# controller.net
KiCad netlist of a schematic drawn in EAGLE
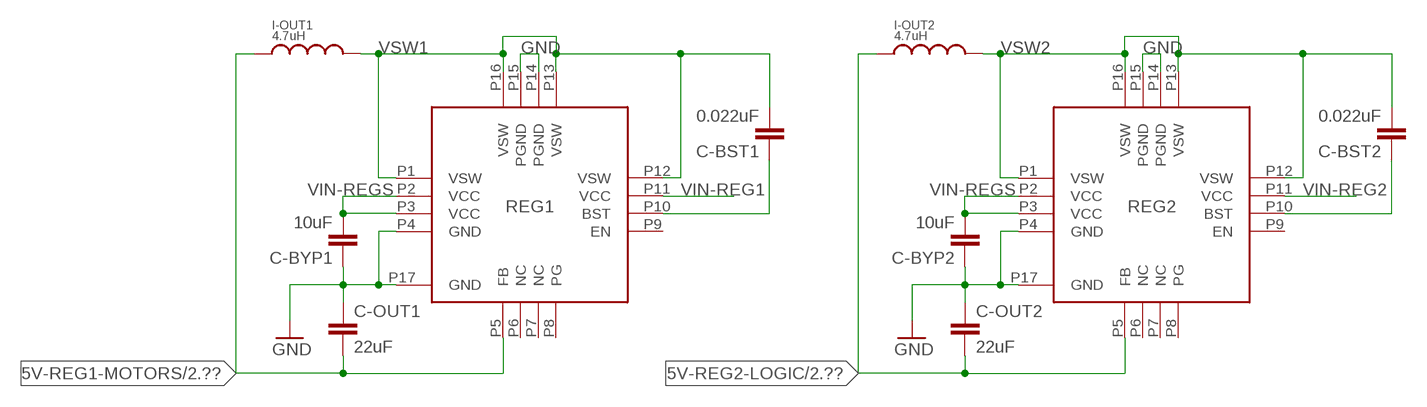
[diagram p0: schematic, sheet 1]
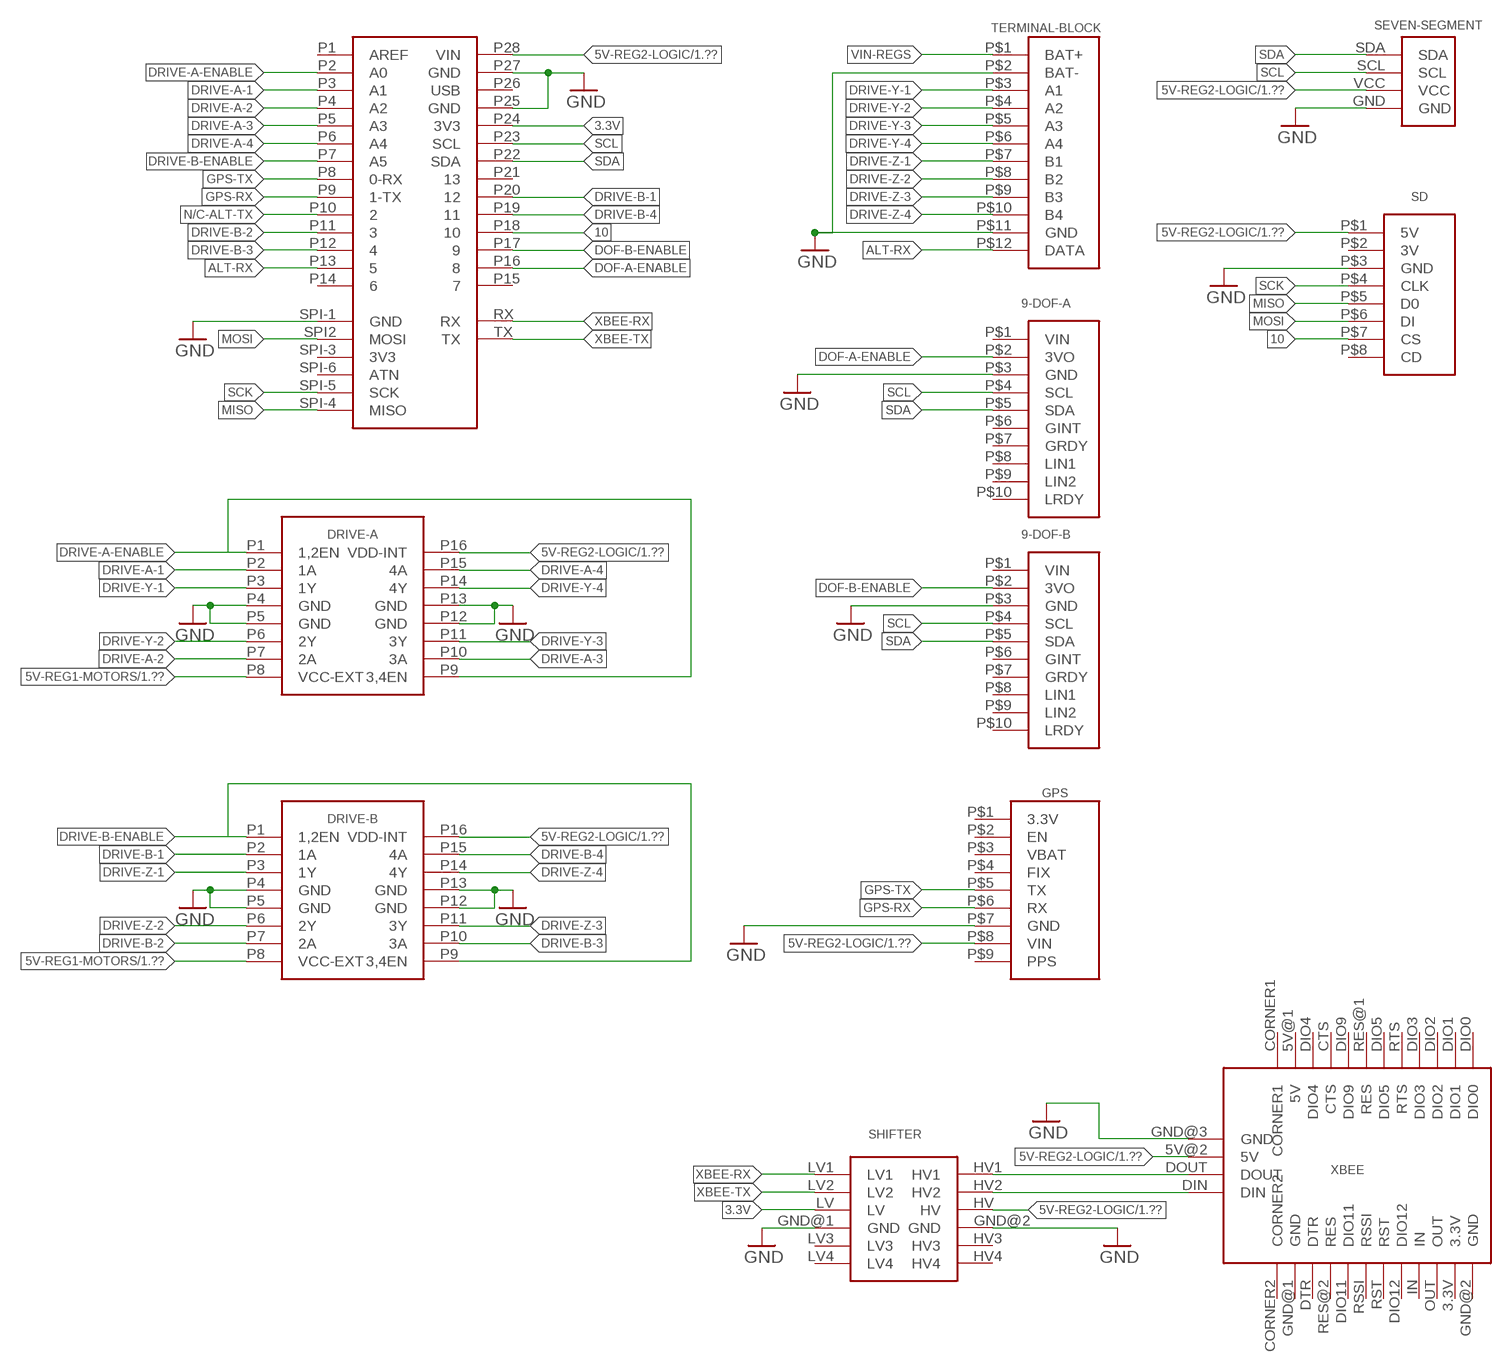
[diagram p1: schematic, sheet 2]

(export (version "E")
  (design (tool "Eeschema 10.0.6"))
  (components
    (comp (ref "9-DOF-A")
      (value "ADAFRUIT-9-DOF")
      (footprint "eagle-import:ADAFRUIT-9-DOF")
      (fields (field (name "MANF") "Adafruit"))
      (libsource (lib "eagle-import") (part "ADAFRUIT-9-DOF"))
    )
    (comp (ref "9-DOF-B")
      (value "ADAFRUIT-9-DOF")
      (footprint "eagle-import:ADAFRUIT-9-DOF")
      (fields (field (name "MANF") "Adafruit"))
      (libsource (lib "eagle-import") (part "ADAFRUIT-9-DOF"))
    )
    (comp (ref "DRIVE-A")
      (value "SN754410")
      (footprint "eagle-import:SN754410")
      (fields (field (name "MANF") "Texas Instruments"))
      (libsource (lib "eagle-import") (part "SN754410"))
    )
    (comp (ref "DRIVE-B")
      (value "SN754410")
      (footprint "eagle-import:SN754410")
      (fields (field (name "MANF") "Texas Instruments"))
      (libsource (lib "eagle-import") (part "SN754410"))
    )
    (comp (ref "GPS")
      (value "ADAFRUIT-GPS-BREAKOUT")
      (footprint "eagle-import:ADAFRUIT-GPS-BREAKOUT")
      (libsource (lib "eagle-import") (part "ADAFRUIT-GPS-BREAKOUT"))
    )
    (comp (ref "NEUTRINO")
      (value "NEUTRINO")
      (footprint "eagle-import:NEUTRINO")
      (libsource (lib "eagle-import") (part "NEUTRINO"))
    )
    (comp (ref "SD")
      (value "ADAFRUIT-MICRO-SD")
      (footprint "eagle-import:ADAFRUIT-MICRO-SD")
      (libsource (lib "eagle-import") (part "ADAFRUIT-MICRO-SD"))
    )
    (comp (ref "SEVEN-SEGMENT")
      (value "ADAFRUIT-7-SEGMENT")
      (footprint "eagle-import:ADAFRUIT-7-SEGMENT")
      (libsource (lib "eagle-import") (part "ADAFRUIT-7-SEGMENT"))
    )
    (comp (ref "SHIFTER")
      (value "SPARKFUN-LEVEL-SHIFTER")
      (footprint "eagle-import:SPARKFUN-LEVEL-SHIFTER")
      (libsource (lib "eagle-import") (part "SPARKFUN-LEVEL-SHIFTER"))
    )
    (comp (ref "TERMINAL-BLOCK")
      (value "1725753")
      (footprint "eagle-import:1725753")
      (fields (field (name "MANF") "Phoenix Contact"))
      (libsource (lib "eagle-import") (part "1725753"))
    )
    (comp (ref "XBEE")
      (value "XBEE-BREAKOUT")
      (footprint "eagle-import:XBEE-BREAKOUT")
      (libsource (lib "eagle-import") (part "XBEE-BREAKOUT"))
    )
    (comp (ref "C-BST1")
      (value "0.022uF")
      (footprint "eagle-import:C1608")
      (fields (field (name "MANF") "Samsung Electro-Mechanics America, Inc."))
      (libsource (lib "eagle-import") (part "C-EUC1608"))
    )
    (comp (ref "C-BST2")
      (value "0.022uF")
      (footprint "eagle-import:C1608")
      (fields (field (name "MANF") "Samsung Electro-Mechanics America, Inc."))
      (libsource (lib "eagle-import") (part "C-EUC1608"))
    )
    (comp (ref "C-BYP1")
      (value "10uF")
      (footprint "eagle-import:C3216")
      (fields (field (name "MANF") "Murata Electronics North America"))
      (libsource (lib "eagle-import") (part "C-EUC3216"))
    )
    (comp (ref "C-BYP2")
      (value "10uF")
      (footprint "eagle-import:C3216")
      (fields (field (name "MANF") "Murata Electronics North America"))
      (libsource (lib "eagle-import") (part "C-EUC3216"))
    )
    (comp (ref "C-OUT1")
      (value "22uF")
      (footprint "eagle-import:C2012")
      (fields (field (name "MANF") "TDK Corporation"))
      (libsource (lib "eagle-import") (part "C-EUC2012"))
    )
    (comp (ref "C-OUT2")
      (value "22uF")
      (footprint "eagle-import:C2012")
      (fields (field (name "MANF") "TDK Corporation"))
      (libsource (lib "eagle-import") (part "C-EUC2012"))
    )
    (comp (ref "I-OUT1")
      (value "4.7uH")
      (footprint "eagle-import:ASPI-0628-4R7M-T1")
      (fields (field (name "MANF") "Abracon LLC"))
      (libsource (lib "eagle-import") (part "ASPI-0628-4R7M-T1"))
    )
    (comp (ref "I-OUT2")
      (value "4.7uH")
      (footprint "eagle-import:ASPI-0628-4R7M-T1")
      (fields (field (name "MANF") "Abracon LLC"))
      (libsource (lib "eagle-import") (part "ASPI-0628-4R7M-T1"))
    )
    (comp (ref "REG1")
      (value "TS30012-M050QFNR")
      (footprint "eagle-import:TS30012-M050QFNR")
      (fields (field (name "MANF") "Semtech Corporation"))
      (libsource (lib "eagle-import") (part "TS30012-M050QFNR"))
    )
    (comp (ref "REG2")
      (value "TS30012-M050QFNR")
      (footprint "eagle-import:TS30012-M050QFNR")
      (fields (field (name "MANF") "Semtech Corporation"))
      (libsource (lib "eagle-import") (part "TS30012-M050QFNR"))
    )
  )
  (nets
    (net (code "1") (name "3.3V") (class "Default")
      (node (ref "NEUTRINO") (pin "P24") (pinfunction "3V3_P24") (pintype "bidirectional"))
      (node (ref "SHIFTER") (pin "LV") (pinfunction "LV_LV") (pintype "bidirectional"))
    )
    (net (code "2") (name "5V-REG1-MOTORS") (class "Default")
      (node (ref "C-OUT1") (pin "2") (pinfunction "2_2") (pintype "passive"))
      (node (ref "DRIVE-A") (pin "P8") (pinfunction "VCC-EXT_P8") (pintype "bidirectional"))
      (node (ref "DRIVE-B") (pin "P8") (pinfunction "VCC-EXT_P8") (pintype "bidirectional"))
      (node (ref "I-OUT1") (pin "P$1") (pinfunction "P$1_P$1") (pintype "bidirectional"))
      (node (ref "REG1") (pin "P5") (pinfunction "FB_P5") (pintype "bidirectional"))
    )
    (net (code "3") (name "5V-REG2-LOGIC") (class "Default")
      (node (ref "C-OUT2") (pin "2") (pinfunction "2_2") (pintype "passive"))
      (node (ref "DRIVE-A") (pin "P16") (pinfunction "VDD-INT_P16") (pintype "bidirectional"))
      (node (ref "DRIVE-B") (pin "P16") (pinfunction "VDD-INT_P16") (pintype "bidirectional"))
      (node (ref "GPS") (pin "P$8") (pinfunction "VIN_P$8") (pintype "bidirectional"))
      (node (ref "I-OUT2") (pin "P$1") (pinfunction "P$1_P$1") (pintype "bidirectional"))
      (node (ref "NEUTRINO") (pin "P28") (pinfunction "VIN_P28") (pintype "bidirectional"))
      (node (ref "REG2") (pin "P5") (pinfunction "FB_P5") (pintype "bidirectional"))
      (node (ref "SD") (pin "P$1") (pinfunction "5V_P$1") (pintype "bidirectional"))
      (node (ref "SEVEN-SEGMENT") (pin "VCC") (pinfunction "VCC_VCC") (pintype "bidirectional"))
      (node (ref "SHIFTER") (pin "HV") (pinfunction "HV_HV") (pintype "bidirectional"))
      (node (ref "XBEE") (pin "5V@2") (pinfunction "5V_5V@2") (pintype "bidirectional"))
    )
    (net (code "4") (name "10") (class "Default")
      (node (ref "NEUTRINO") (pin "P18") (pinfunction "10_P18") (pintype "bidirectional"))
      (node (ref "SD") (pin "P$7") (pinfunction "CS_P$7") (pintype "bidirectional"))
    )
    (net (code "5") (name "ALT-RX") (class "Default")
      (node (ref "NEUTRINO") (pin "P13") (pinfunction "5_P13") (pintype "bidirectional"))
      (node (ref "TERMINAL-BLOCK") (pin "P$12") (pinfunction "DATA_P$12") (pintype "bidirectional"))
    )
    (net (code "6") (name "DOF-A-ENABLE") (class "Default")
      (node (ref "9-DOF-A") (pin "P$2") (pinfunction "3VO_P$2") (pintype "bidirectional"))
      (node (ref "NEUTRINO") (pin "P16") (pinfunction "8_P16") (pintype "bidirectional"))
    )
    (net (code "7") (name "DOF-B-ENABLE") (class "Default")
      (node (ref "9-DOF-B") (pin "P$2") (pinfunction "3VO_P$2") (pintype "bidirectional"))
      (node (ref "NEUTRINO") (pin "P17") (pinfunction "9_P17") (pintype "bidirectional"))
    )
    (net (code "8") (name "DRIVE-A-1") (class "Default")
      (node (ref "DRIVE-A") (pin "P2") (pinfunction "1A_P2") (pintype "bidirectional"))
      (node (ref "NEUTRINO") (pin "P3") (pinfunction "A1_P3") (pintype "bidirectional"))
    )
    (net (code "9") (name "DRIVE-A-2") (class "Default")
      (node (ref "DRIVE-A") (pin "P7") (pinfunction "2A_P7") (pintype "bidirectional"))
      (node (ref "NEUTRINO") (pin "P4") (pinfunction "A2_P4") (pintype "bidirectional"))
    )
    (net (code "10") (name "DRIVE-A-3") (class "Default")
      (node (ref "DRIVE-A") (pin "P10") (pinfunction "3A_P10") (pintype "bidirectional"))
      (node (ref "NEUTRINO") (pin "P5") (pinfunction "A3_P5") (pintype "bidirectional"))
    )
    (net (code "11") (name "DRIVE-A-4") (class "Default")
      (node (ref "DRIVE-A") (pin "P15") (pinfunction "4A_P15") (pintype "bidirectional"))
      (node (ref "NEUTRINO") (pin "P6") (pinfunction "A4_P6") (pintype "bidirectional"))
    )
    (net (code "12") (name "DRIVE-A-ENABLE") (class "Default")
      (node (ref "DRIVE-A") (pin "P1") (pinfunction "1,2EN_P1") (pintype "bidirectional"))
      (node (ref "DRIVE-A") (pin "P9") (pinfunction "3,4EN_P9") (pintype "bidirectional"))
      (node (ref "NEUTRINO") (pin "P2") (pinfunction "A0_P2") (pintype "bidirectional"))
    )
    (net (code "13") (name "DRIVE-B-1") (class "Default")
      (node (ref "DRIVE-B") (pin "P2") (pinfunction "1A_P2") (pintype "bidirectional"))
      (node (ref "NEUTRINO") (pin "P20") (pinfunction "12_P20") (pintype "bidirectional"))
    )
    (net (code "14") (name "DRIVE-B-2") (class "Default")
      (node (ref "DRIVE-B") (pin "P7") (pinfunction "2A_P7") (pintype "bidirectional"))
      (node (ref "NEUTRINO") (pin "P11") (pinfunction "3_P11") (pintype "bidirectional"))
    )
    (net (code "15") (name "DRIVE-B-3") (class "Default")
      (node (ref "DRIVE-B") (pin "P10") (pinfunction "3A_P10") (pintype "bidirectional"))
      (node (ref "NEUTRINO") (pin "P12") (pinfunction "4_P12") (pintype "bidirectional"))
    )
    (net (code "16") (name "DRIVE-B-4") (class "Default")
      (node (ref "DRIVE-B") (pin "P15") (pinfunction "4A_P15") (pintype "bidirectional"))
      (node (ref "NEUTRINO") (pin "P19") (pinfunction "11_P19") (pintype "bidirectional"))
    )
    (net (code "17") (name "DRIVE-B-ENABLE") (class "Default")
      (node (ref "DRIVE-B") (pin "P1") (pinfunction "1,2EN_P1") (pintype "bidirectional"))
      (node (ref "DRIVE-B") (pin "P9") (pinfunction "3,4EN_P9") (pintype "bidirectional"))
      (node (ref "NEUTRINO") (pin "P7") (pinfunction "A5_P7") (pintype "bidirectional"))
    )
    (net (code "18") (name "DRIVE-Y-1") (class "Default")
      (node (ref "DRIVE-A") (pin "P3") (pinfunction "1Y_P3") (pintype "bidirectional"))
      (node (ref "TERMINAL-BLOCK") (pin "P$3") (pinfunction "A1_P$3") (pintype "bidirectional"))
    )
    (net (code "19") (name "DRIVE-Y-2") (class "Default")
      (node (ref "DRIVE-A") (pin "P6") (pinfunction "2Y_P6") (pintype "bidirectional"))
      (node (ref "TERMINAL-BLOCK") (pin "P$4") (pinfunction "A2_P$4") (pintype "bidirectional"))
    )
    (net (code "20") (name "DRIVE-Y-3") (class "Default")
      (node (ref "DRIVE-A") (pin "P11") (pinfunction "3Y_P11") (pintype "bidirectional"))
      (node (ref "TERMINAL-BLOCK") (pin "P$5") (pinfunction "A3_P$5") (pintype "bidirectional"))
    )
    (net (code "21") (name "DRIVE-Y-4") (class "Default")
      (node (ref "DRIVE-A") (pin "P14") (pinfunction "4Y_P14") (pintype "bidirectional"))
      (node (ref "TERMINAL-BLOCK") (pin "P$6") (pinfunction "A4_P$6") (pintype "bidirectional"))
    )
    (net (code "22") (name "DRIVE-Z-1") (class "Default")
      (node (ref "DRIVE-B") (pin "P3") (pinfunction "1Y_P3") (pintype "bidirectional"))
      (node (ref "TERMINAL-BLOCK") (pin "P$7") (pinfunction "B1_P$7") (pintype "bidirectional"))
    )
    (net (code "23") (name "DRIVE-Z-2") (class "Default")
      (node (ref "DRIVE-B") (pin "P6") (pinfunction "2Y_P6") (pintype "bidirectional"))
      (node (ref "TERMINAL-BLOCK") (pin "P$8") (pinfunction "B2_P$8") (pintype "bidirectional"))
    )
    (net (code "24") (name "DRIVE-Z-3") (class "Default")
      (node (ref "DRIVE-B") (pin "P11") (pinfunction "3Y_P11") (pintype "bidirectional"))
      (node (ref "TERMINAL-BLOCK") (pin "P$9") (pinfunction "B3_P$9") (pintype "bidirectional"))
    )
    (net (code "25") (name "DRIVE-Z-4") (class "Default")
      (node (ref "DRIVE-B") (pin "P14") (pinfunction "4Y_P14") (pintype "bidirectional"))
      (node (ref "TERMINAL-BLOCK") (pin "P$10") (pinfunction "B4_P$10") (pintype "bidirectional"))
    )
    (net (code "26") (name "GND") (class "Default")
      (node (ref "9-DOF-A") (pin "P$3") (pinfunction "GND_P$3") (pintype "bidirectional"))
      (node (ref "9-DOF-B") (pin "P$3") (pinfunction "GND_P$3") (pintype "bidirectional"))
      (node (ref "C-BYP1") (pin "1") (pinfunction "1_1") (pintype "passive"))
      (node (ref "C-BYP2") (pin "1") (pinfunction "1_1") (pintype "passive"))
      (node (ref "C-OUT1") (pin "1") (pinfunction "1_1") (pintype "passive"))
      (node (ref "C-OUT2") (pin "1") (pinfunction "1_1") (pintype "passive"))
      (node (ref "DRIVE-A") (pin "P12") (pinfunction "GND_P12") (pintype "bidirectional"))
      (node (ref "DRIVE-A") (pin "P13") (pinfunction "GND_P13") (pintype "bidirectional"))
      (node (ref "DRIVE-A") (pin "P4") (pinfunction "GND_P4") (pintype "bidirectional"))
      (node (ref "DRIVE-A") (pin "P5") (pinfunction "GND_P5") (pintype "bidirectional"))
      (node (ref "DRIVE-B") (pin "P12") (pinfunction "GND_P12") (pintype "bidirectional"))
      (node (ref "DRIVE-B") (pin "P13") (pinfunction "GND_P13") (pintype "bidirectional"))
      (node (ref "DRIVE-B") (pin "P4") (pinfunction "GND_P4") (pintype "bidirectional"))
      (node (ref "DRIVE-B") (pin "P5") (pinfunction "GND_P5") (pintype "bidirectional"))
      (node (ref "GPS") (pin "P$7") (pinfunction "GND_P$7") (pintype "bidirectional"))
      (node (ref "NEUTRINO") (pin "P25") (pinfunction "GND_P25") (pintype "bidirectional"))
      (node (ref "NEUTRINO") (pin "P27") (pinfunction "GND_P27") (pintype "bidirectional"))
      (node (ref "NEUTRINO") (pin "SPI-1") (pinfunction "GND_SPI-1") (pintype "bidirectional"))
      (node (ref "REG1") (pin "P14") (pinfunction "PGND_P14") (pintype "bidirectional"))
      (node (ref "REG1") (pin "P15") (pinfunction "PGND_P15") (pintype "bidirectional"))
      (node (ref "REG1") (pin "P17") (pinfunction "GND_P17") (pintype "bidirectional"))
      (node (ref "REG1") (pin "P4") (pinfunction "GND_P4") (pintype "bidirectional"))
      (node (ref "REG2") (pin "P14") (pinfunction "PGND_P14") (pintype "bidirectional"))
      (node (ref "REG2") (pin "P15") (pinfunction "PGND_P15") (pintype "bidirectional"))
      (node (ref "REG2") (pin "P17") (pinfunction "GND_P17") (pintype "bidirectional"))
      (node (ref "REG2") (pin "P4") (pinfunction "GND_P4") (pintype "bidirectional"))
      (node (ref "SD") (pin "P$3") (pinfunction "GND_P$3") (pintype "bidirectional"))
      (node (ref "SEVEN-SEGMENT") (pin "GND") (pinfunction "GND_GND") (pintype "bidirectional"))
      (node (ref "SHIFTER") (pin "GND@1") (pinfunction "GND_GND@1") (pintype "bidirectional"))
      (node (ref "SHIFTER") (pin "GND@2") (pinfunction "GND_GND@2") (pintype "bidirectional"))
      (node (ref "TERMINAL-BLOCK") (pin "P$11") (pinfunction "GND_P$11") (pintype "bidirectional"))
      (node (ref "TERMINAL-BLOCK") (pin "P$2") (pinfunction "BAT-_P$2") (pintype "bidirectional"))
      (node (ref "XBEE") (pin "GND@3") (pinfunction "GND_GND@3") (pintype "bidirectional"))
    )
    (net (code "27") (name "GPS-RX") (class "Default")
      (node (ref "GPS") (pin "P$6") (pinfunction "RX_P$6") (pintype "bidirectional"))
      (node (ref "NEUTRINO") (pin "P9") (pinfunction "1-TX_P9") (pintype "bidirectional"))
    )
    (net (code "28") (name "GPS-TX") (class "Default")
      (node (ref "GPS") (pin "P$5") (pinfunction "TX_P$5") (pintype "bidirectional"))
      (node (ref "NEUTRINO") (pin "P8") (pinfunction "0-RX_P8") (pintype "bidirectional"))
    )
    (net (code "29") (name "MISO") (class "Default")
      (node (ref "NEUTRINO") (pin "SPI-4") (pinfunction "MISO_SPI-4") (pintype "bidirectional"))
      (node (ref "SD") (pin "P$5") (pinfunction "D0_P$5") (pintype "bidirectional"))
    )
    (net (code "30") (name "MOSI") (class "Default")
      (node (ref "NEUTRINO") (pin "SPI2") (pinfunction "MOSI_SPI2") (pintype "bidirectional"))
      (node (ref "SD") (pin "P$6") (pinfunction "DI_P$6") (pintype "bidirectional"))
    )
    (net (code "31") (name "Net-(REG1-BST)") (class "Default")
      (node (ref "C-BST1") (pin "1") (pinfunction "1_1") (pintype "passive"))
      (node (ref "REG1") (pin "P10") (pinfunction "BST_P10") (pintype "bidirectional"))
    )
    (net (code "32") (name "Net-(REG2-BST)") (class "Default")
      (node (ref "C-BST2") (pin "1") (pinfunction "1_1") (pintype "passive"))
      (node (ref "REG2") (pin "P10") (pinfunction "BST_P10") (pintype "bidirectional"))
    )
    (net (code "33") (name "Net-(SHIFTER-PadHV1)") (class "Default")
      (node (ref "SHIFTER") (pin "HV1") (pinfunction "HV1_HV1") (pintype "bidirectional"))
      (node (ref "XBEE") (pin "DOUT") (pinfunction "DOUT_DOUT") (pintype "bidirectional"))
    )
    (net (code "34") (name "Net-(SHIFTER-PadHV2)") (class "Default")
      (node (ref "SHIFTER") (pin "HV2") (pinfunction "HV2_HV2") (pintype "bidirectional"))
      (node (ref "XBEE") (pin "DIN") (pinfunction "DIN_DIN") (pintype "bidirectional"))
    )
    (net (code "35") (name "N{slash}C-ALT-TX") (class "Default")
      (node (ref "NEUTRINO") (pin "P10") (pinfunction "2_P10") (pintype "bidirectional"))
    )
    (net (code "36") (name "SCK") (class "Default")
      (node (ref "NEUTRINO") (pin "SPI-5") (pinfunction "SCK_SPI-5") (pintype "bidirectional"))
      (node (ref "SD") (pin "P$4") (pinfunction "CLK_P$4") (pintype "bidirectional"))
    )
    (net (code "37") (name "SCL") (class "Default")
      (node (ref "9-DOF-A") (pin "P$4") (pinfunction "SCL_P$4") (pintype "bidirectional"))
      (node (ref "9-DOF-B") (pin "P$4") (pinfunction "SCL_P$4") (pintype "bidirectional"))
      (node (ref "NEUTRINO") (pin "P23") (pinfunction "SCL_P23") (pintype "bidirectional"))
      (node (ref "SEVEN-SEGMENT") (pin "SCL") (pinfunction "SCL_SCL") (pintype "bidirectional"))
    )
    (net (code "38") (name "SDA") (class "Default")
      (node (ref "9-DOF-A") (pin "P$5") (pinfunction "SDA_P$5") (pintype "bidirectional"))
      (node (ref "9-DOF-B") (pin "P$5") (pinfunction "SDA_P$5") (pintype "bidirectional"))
      (node (ref "NEUTRINO") (pin "P22") (pinfunction "SDA_P22") (pintype "bidirectional"))
      (node (ref "SEVEN-SEGMENT") (pin "SDA") (pinfunction "SDA_SDA") (pintype "bidirectional"))
    )
    (net (code "39") (name "VIN-REG1") (class "Default")
      (node (ref "REG1") (pin "P11") (pinfunction "VCC_P11") (pintype "bidirectional"))
    )
    (net (code "40") (name "VIN-REG2") (class "Default")
      (node (ref "REG2") (pin "P11") (pinfunction "VCC_P11") (pintype "bidirectional"))
    )
    (net (code "41") (name "VIN-REGS") (class "Default")
      (node (ref "C-BYP1") (pin "2") (pinfunction "2_2") (pintype "passive"))
      (node (ref "C-BYP2") (pin "2") (pinfunction "2_2") (pintype "passive"))
      (node (ref "REG1") (pin "P2") (pinfunction "VCC_P2") (pintype "bidirectional"))
      (node (ref "REG1") (pin "P3") (pinfunction "VCC_P3") (pintype "bidirectional"))
      (node (ref "REG2") (pin "P2") (pinfunction "VCC_P2") (pintype "bidirectional"))
      (node (ref "REG2") (pin "P3") (pinfunction "VCC_P3") (pintype "bidirectional"))
      (node (ref "TERMINAL-BLOCK") (pin "P$1") (pinfunction "BAT+_P$1") (pintype "bidirectional"))
    )
    (net (code "42") (name "VSW1") (class "Default")
      (node (ref "C-BST1") (pin "2") (pinfunction "2_2") (pintype "passive"))
      (node (ref "I-OUT1") (pin "P$2") (pinfunction "P$2_P$2") (pintype "bidirectional"))
      (node (ref "REG1") (pin "P1") (pinfunction "VSW_P1") (pintype "bidirectional"))
      (node (ref "REG1") (pin "P12") (pinfunction "VSW_P12") (pintype "bidirectional"))
      (node (ref "REG1") (pin "P13") (pinfunction "VSW_P13") (pintype "bidirectional"))
      (node (ref "REG1") (pin "P16") (pinfunction "VSW_P16") (pintype "bidirectional"))
    )
    (net (code "43") (name "VSW2") (class "Default")
      (node (ref "C-BST2") (pin "2") (pinfunction "2_2") (pintype "passive"))
      (node (ref "I-OUT2") (pin "P$2") (pinfunction "P$2_P$2") (pintype "bidirectional"))
      (node (ref "REG2") (pin "P1") (pinfunction "VSW_P1") (pintype "bidirectional"))
      (node (ref "REG2") (pin "P12") (pinfunction "VSW_P12") (pintype "bidirectional"))
      (node (ref "REG2") (pin "P13") (pinfunction "VSW_P13") (pintype "bidirectional"))
      (node (ref "REG2") (pin "P16") (pinfunction "VSW_P16") (pintype "bidirectional"))
    )
    (net (code "44") (name "XBEE-RX") (class "Default")
      (node (ref "NEUTRINO") (pin "RX") (pinfunction "RX_RX") (pintype "bidirectional"))
      (node (ref "SHIFTER") (pin "LV1") (pinfunction "LV1_LV1") (pintype "bidirectional"))
    )
    (net (code "45") (name "XBEE-TX") (class "Default")
      (node (ref "NEUTRINO") (pin "TX") (pinfunction "TX_TX") (pintype "bidirectional"))
      (node (ref "SHIFTER") (pin "LV2") (pinfunction "LV2_LV2") (pintype "bidirectional"))
    )
    (net (code "46") (name "unconnected-(9-DOF-A-GINT-PadP$6)") (class "Default")
      (node (ref "9-DOF-A") (pin "P$6") (pinfunction "GINT_P$6") (pintype "bidirectional"))
    )
    (net (code "47") (name "unconnected-(9-DOF-A-GRDY-PadP$7)") (class "Default")
      (node (ref "9-DOF-A") (pin "P$7") (pinfunction "GRDY_P$7") (pintype "bidirectional"))
    )
    (net (code "48") (name "unconnected-(9-DOF-A-LIN1-PadP$8)") (class "Default")
      (node (ref "9-DOF-A") (pin "P$8") (pinfunction "LIN1_P$8") (pintype "bidirectional"))
    )
    (net (code "49") (name "unconnected-(9-DOF-A-LIN2-PadP$9)") (class "Default")
      (node (ref "9-DOF-A") (pin "P$9") (pinfunction "LIN2_P$9") (pintype "bidirectional"))
    )
    (net (code "50") (name "unconnected-(9-DOF-A-LRDY-PadP$10)") (class "Default")
      (node (ref "9-DOF-A") (pin "P$10") (pinfunction "LRDY_P$10") (pintype "bidirectional"))
    )
    (net (code "51") (name "unconnected-(9-DOF-A-VIN-PadP$1)") (class "Default")
      (node (ref "9-DOF-A") (pin "P$1") (pinfunction "VIN_P$1") (pintype "bidirectional"))
    )
    (net (code "52") (name "unconnected-(9-DOF-B-GINT-PadP$6)") (class "Default")
      (node (ref "9-DOF-B") (pin "P$6") (pinfunction "GINT_P$6") (pintype "bidirectional"))
    )
    (net (code "53") (name "unconnected-(9-DOF-B-GRDY-PadP$7)") (class "Default")
      (node (ref "9-DOF-B") (pin "P$7") (pinfunction "GRDY_P$7") (pintype "bidirectional"))
    )
    (net (code "54") (name "unconnected-(9-DOF-B-LIN1-PadP$8)") (class "Default")
      (node (ref "9-DOF-B") (pin "P$8") (pinfunction "LIN1_P$8") (pintype "bidirectional"))
    )
    (net (code "55") (name "unconnected-(9-DOF-B-LIN2-PadP$9)") (class "Default")
      (node (ref "9-DOF-B") (pin "P$9") (pinfunction "LIN2_P$9") (pintype "bidirectional"))
    )
    (net (code "56") (name "unconnected-(9-DOF-B-LRDY-PadP$10)") (class "Default")
      (node (ref "9-DOF-B") (pin "P$10") (pinfunction "LRDY_P$10") (pintype "bidirectional"))
    )
    (net (code "57") (name "unconnected-(9-DOF-B-VIN-PadP$1)") (class "Default")
      (node (ref "9-DOF-B") (pin "P$1") (pinfunction "VIN_P$1") (pintype "bidirectional"))
    )
    (net (code "58") (name "unconnected-(GPS-3.3V-PadP$1)") (class "Default")
      (node (ref "GPS") (pin "P$1") (pinfunction "3.3V_P$1") (pintype "bidirectional"))
    )
    (net (code "59") (name "unconnected-(GPS-EN-PadP$2)") (class "Default")
      (node (ref "GPS") (pin "P$2") (pinfunction "EN_P$2") (pintype "bidirectional"))
    )
    (net (code "60") (name "unconnected-(GPS-FIX-PadP$4)") (class "Default")
      (node (ref "GPS") (pin "P$4") (pinfunction "FIX_P$4") (pintype "bidirectional"))
    )
    (net (code "61") (name "unconnected-(GPS-PPS-PadP$9)") (class "Default")
      (node (ref "GPS") (pin "P$9") (pinfunction "PPS_P$9") (pintype "bidirectional"))
    )
    (net (code "62") (name "unconnected-(GPS-VBAT-PadP$3)") (class "Default")
      (node (ref "GPS") (pin "P$3") (pinfunction "VBAT_P$3") (pintype "bidirectional"))
    )
    (net (code "63") (name "unconnected-(NEUTRINO-3V3-PadSPI-3)") (class "Default")
      (node (ref "NEUTRINO") (pin "SPI-3") (pinfunction "3V3_SPI-3") (pintype "bidirectional"))
    )
    (net (code "64") (name "unconnected-(NEUTRINO-6-PadP14)") (class "Default")
      (node (ref "NEUTRINO") (pin "P14") (pinfunction "6_P14") (pintype "bidirectional"))
    )
    (net (code "65") (name "unconnected-(NEUTRINO-7-PadP15)") (class "Default")
      (node (ref "NEUTRINO") (pin "P15") (pinfunction "7_P15") (pintype "bidirectional"))
    )
    (net (code "66") (name "unconnected-(NEUTRINO-13-PadP21)") (class "Default")
      (node (ref "NEUTRINO") (pin "P21") (pinfunction "13_P21") (pintype "bidirectional"))
    )
    (net (code "67") (name "unconnected-(NEUTRINO-AREF-PadP1)") (class "Default")
      (node (ref "NEUTRINO") (pin "P1") (pinfunction "AREF_P1") (pintype "bidirectional"))
    )
    (net (code "68") (name "unconnected-(NEUTRINO-ATN-PadSPI-6)") (class "Default")
      (node (ref "NEUTRINO") (pin "SPI-6") (pinfunction "ATN_SPI-6") (pintype "bidirectional"))
    )
    (net (code "69") (name "unconnected-(NEUTRINO-USB-PadP26)") (class "Default")
      (node (ref "NEUTRINO") (pin "P26") (pinfunction "USB_P26") (pintype "bidirectional"))
    )
    (net (code "70") (name "unconnected-(REG1-EN-PadP9)") (class "Default")
      (node (ref "REG1") (pin "P9") (pinfunction "EN_P9") (pintype "bidirectional"))
    )
    (net (code "71") (name "unconnected-(REG1-NC-PadP6)") (class "Default")
      (node (ref "REG1") (pin "P6") (pinfunction "NC_P6") (pintype "bidirectional"))
    )
    (net (code "72") (name "unconnected-(REG1-NC-PadP7)") (class "Default")
      (node (ref "REG1") (pin "P7") (pinfunction "NC_P7") (pintype "bidirectional"))
    )
    (net (code "73") (name "unconnected-(REG1-PG-PadP8)") (class "Default")
      (node (ref "REG1") (pin "P8") (pinfunction "PG_P8") (pintype "bidirectional"))
    )
    (net (code "74") (name "unconnected-(REG2-EN-PadP9)") (class "Default")
      (node (ref "REG2") (pin "P9") (pinfunction "EN_P9") (pintype "bidirectional"))
    )
    (net (code "75") (name "unconnected-(REG2-NC-PadP6)") (class "Default")
      (node (ref "REG2") (pin "P6") (pinfunction "NC_P6") (pintype "bidirectional"))
    )
    (net (code "76") (name "unconnected-(REG2-NC-PadP7)") (class "Default")
      (node (ref "REG2") (pin "P7") (pinfunction "NC_P7") (pintype "bidirectional"))
    )
    (net (code "77") (name "unconnected-(REG2-PG-PadP8)") (class "Default")
      (node (ref "REG2") (pin "P8") (pinfunction "PG_P8") (pintype "bidirectional"))
    )
    (net (code "78") (name "unconnected-(SD-3V-PadP$2)") (class "Default")
      (node (ref "SD") (pin "P$2") (pinfunction "3V_P$2") (pintype "bidirectional"))
    )
    (net (code "79") (name "unconnected-(SD-CD-PadP$8)") (class "Default")
      (node (ref "SD") (pin "P$8") (pinfunction "CD_P$8") (pintype "bidirectional"))
    )
    (net (code "80") (name "unconnected-(SHIFTER-PadHV3)") (class "Default")
      (node (ref "SHIFTER") (pin "HV3") (pinfunction "HV3_HV3") (pintype "bidirectional"))
    )
    (net (code "81") (name "unconnected-(SHIFTER-PadHV4)") (class "Default")
      (node (ref "SHIFTER") (pin "HV4") (pinfunction "HV4_HV4") (pintype "bidirectional"))
    )
    (net (code "82") (name "unconnected-(SHIFTER-PadLV3)") (class "Default")
      (node (ref "SHIFTER") (pin "LV3") (pinfunction "LV3_LV3") (pintype "bidirectional"))
    )
    (net (code "83") (name "unconnected-(SHIFTER-PadLV4)") (class "Default")
      (node (ref "SHIFTER") (pin "LV4") (pinfunction "LV4_LV4") (pintype "bidirectional"))
    )
    (net (code "84") (name "unconnected-(XBEE-5V-Pad5V@1)") (class "Default")
      (node (ref "XBEE") (pin "5V@1") (pinfunction "5V_5V@1") (pintype "bidirectional"))
    )
    (net (code "85") (name "unconnected-(XBEE-GND-PadGND@1)") (class "Default")
      (node (ref "XBEE") (pin "GND@1") (pinfunction "GND_GND@1") (pintype "bidirectional"))
    )
    (net (code "86") (name "unconnected-(XBEE-GND-PadGND@2)") (class "Default")
      (node (ref "XBEE") (pin "GND@2") (pinfunction "GND_GND@2") (pintype "bidirectional"))
    )
    (net (code "87") (name "unconnected-(XBEE-Pad3.3V)") (class "Default")
      (node (ref "XBEE") (pin "3.3V") (pinfunction "3.3V_3.3V") (pintype "bidirectional"))
    )
    (net (code "88") (name "unconnected-(XBEE-PadCORNER1)") (class "Default")
      (node (ref "XBEE") (pin "CORNER1") (pinfunction "CORNER1_CORNER1") (pintype "bidirectional"))
    )
    (net (code "89") (name "unconnected-(XBEE-PadCORNER2)") (class "Default")
      (node (ref "XBEE") (pin "CORNER2") (pinfunction "CORNER2_CORNER2") (pintype "bidirectional"))
    )
    (net (code "90") (name "unconnected-(XBEE-PadCTS)") (class "Default")
      (node (ref "XBEE") (pin "CTS") (pinfunction "CTS_CTS") (pintype "bidirectional"))
    )
    (net (code "91") (name "unconnected-(XBEE-PadDIO0)") (class "Default")
      (node (ref "XBEE") (pin "DIO0") (pinfunction "DIO0_DIO0") (pintype "bidirectional"))
    )
    (net (code "92") (name "unconnected-(XBEE-PadDIO1)") (class "Default")
      (node (ref "XBEE") (pin "DIO1") (pinfunction "DIO1_DIO1") (pintype "bidirectional"))
    )
    (net (code "93") (name "unconnected-(XBEE-PadDIO2)") (class "Default")
      (node (ref "XBEE") (pin "DIO2") (pinfunction "DIO2_DIO2") (pintype "bidirectional"))
    )
    (net (code "94") (name "unconnected-(XBEE-PadDIO3)") (class "Default")
      (node (ref "XBEE") (pin "DIO3") (pinfunction "DIO3_DIO3") (pintype "bidirectional"))
    )
    (net (code "95") (name "unconnected-(XBEE-PadDIO4)") (class "Default")
      (node (ref "XBEE") (pin "DIO4") (pinfunction "DIO4_DIO4") (pintype "bidirectional"))
    )
    (net (code "96") (name "unconnected-(XBEE-PadDIO5)") (class "Default")
      (node (ref "XBEE") (pin "DIO5") (pinfunction "DIO5_DIO5") (pintype "bidirectional"))
    )
    (net (code "97") (name "unconnected-(XBEE-PadDIO9)") (class "Default")
      (node (ref "XBEE") (pin "DIO9") (pinfunction "DIO9_DIO9") (pintype "bidirectional"))
    )
    (net (code "98") (name "unconnected-(XBEE-PadDIO11)") (class "Default")
      (node (ref "XBEE") (pin "DIO11") (pinfunction "DIO11_DIO11") (pintype "bidirectional"))
    )
    (net (code "99") (name "unconnected-(XBEE-PadDIO12)") (class "Default")
      (node (ref "XBEE") (pin "DIO12") (pinfunction "DIO12_DIO12") (pintype "bidirectional"))
    )
    (net (code "100") (name "unconnected-(XBEE-PadDTR)") (class "Default")
      (node (ref "XBEE") (pin "DTR") (pinfunction "DTR_DTR") (pintype "bidirectional"))
    )
    (net (code "101") (name "unconnected-(XBEE-PadIN)") (class "Default")
      (node (ref "XBEE") (pin "IN") (pinfunction "IN_IN") (pintype "bidirectional"))
    )
    (net (code "102") (name "unconnected-(XBEE-PadOUT)") (class "Default")
      (node (ref "XBEE") (pin "OUT") (pinfunction "OUT_OUT") (pintype "bidirectional"))
    )
    (net (code "103") (name "unconnected-(XBEE-PadRSSI)") (class "Default")
      (node (ref "XBEE") (pin "RSSI") (pinfunction "RSSI_RSSI") (pintype "bidirectional"))
    )
    (net (code "104") (name "unconnected-(XBEE-PadRST)") (class "Default")
      (node (ref "XBEE") (pin "RST") (pinfunction "RST_RST") (pintype "bidirectional"))
    )
    (net (code "105") (name "unconnected-(XBEE-PadRTS)") (class "Default")
      (node (ref "XBEE") (pin "RTS") (pinfunction "RTS_RTS") (pintype "bidirectional"))
    )
    (net (code "106") (name "unconnected-(XBEE-RES-PadRES@1)") (class "Default")
      (node (ref "XBEE") (pin "RES@1") (pinfunction "RES_RES@1") (pintype "bidirectional"))
    )
    (net (code "107") (name "unconnected-(XBEE-RES-PadRES@2)") (class "Default")
      (node (ref "XBEE") (pin "RES@2") (pinfunction "RES_RES@2") (pintype "bidirectional"))
    )
  )
)
